# capDisChg_v1.net
KiCad netlist of a schematic drawn in EasyEDA Pro
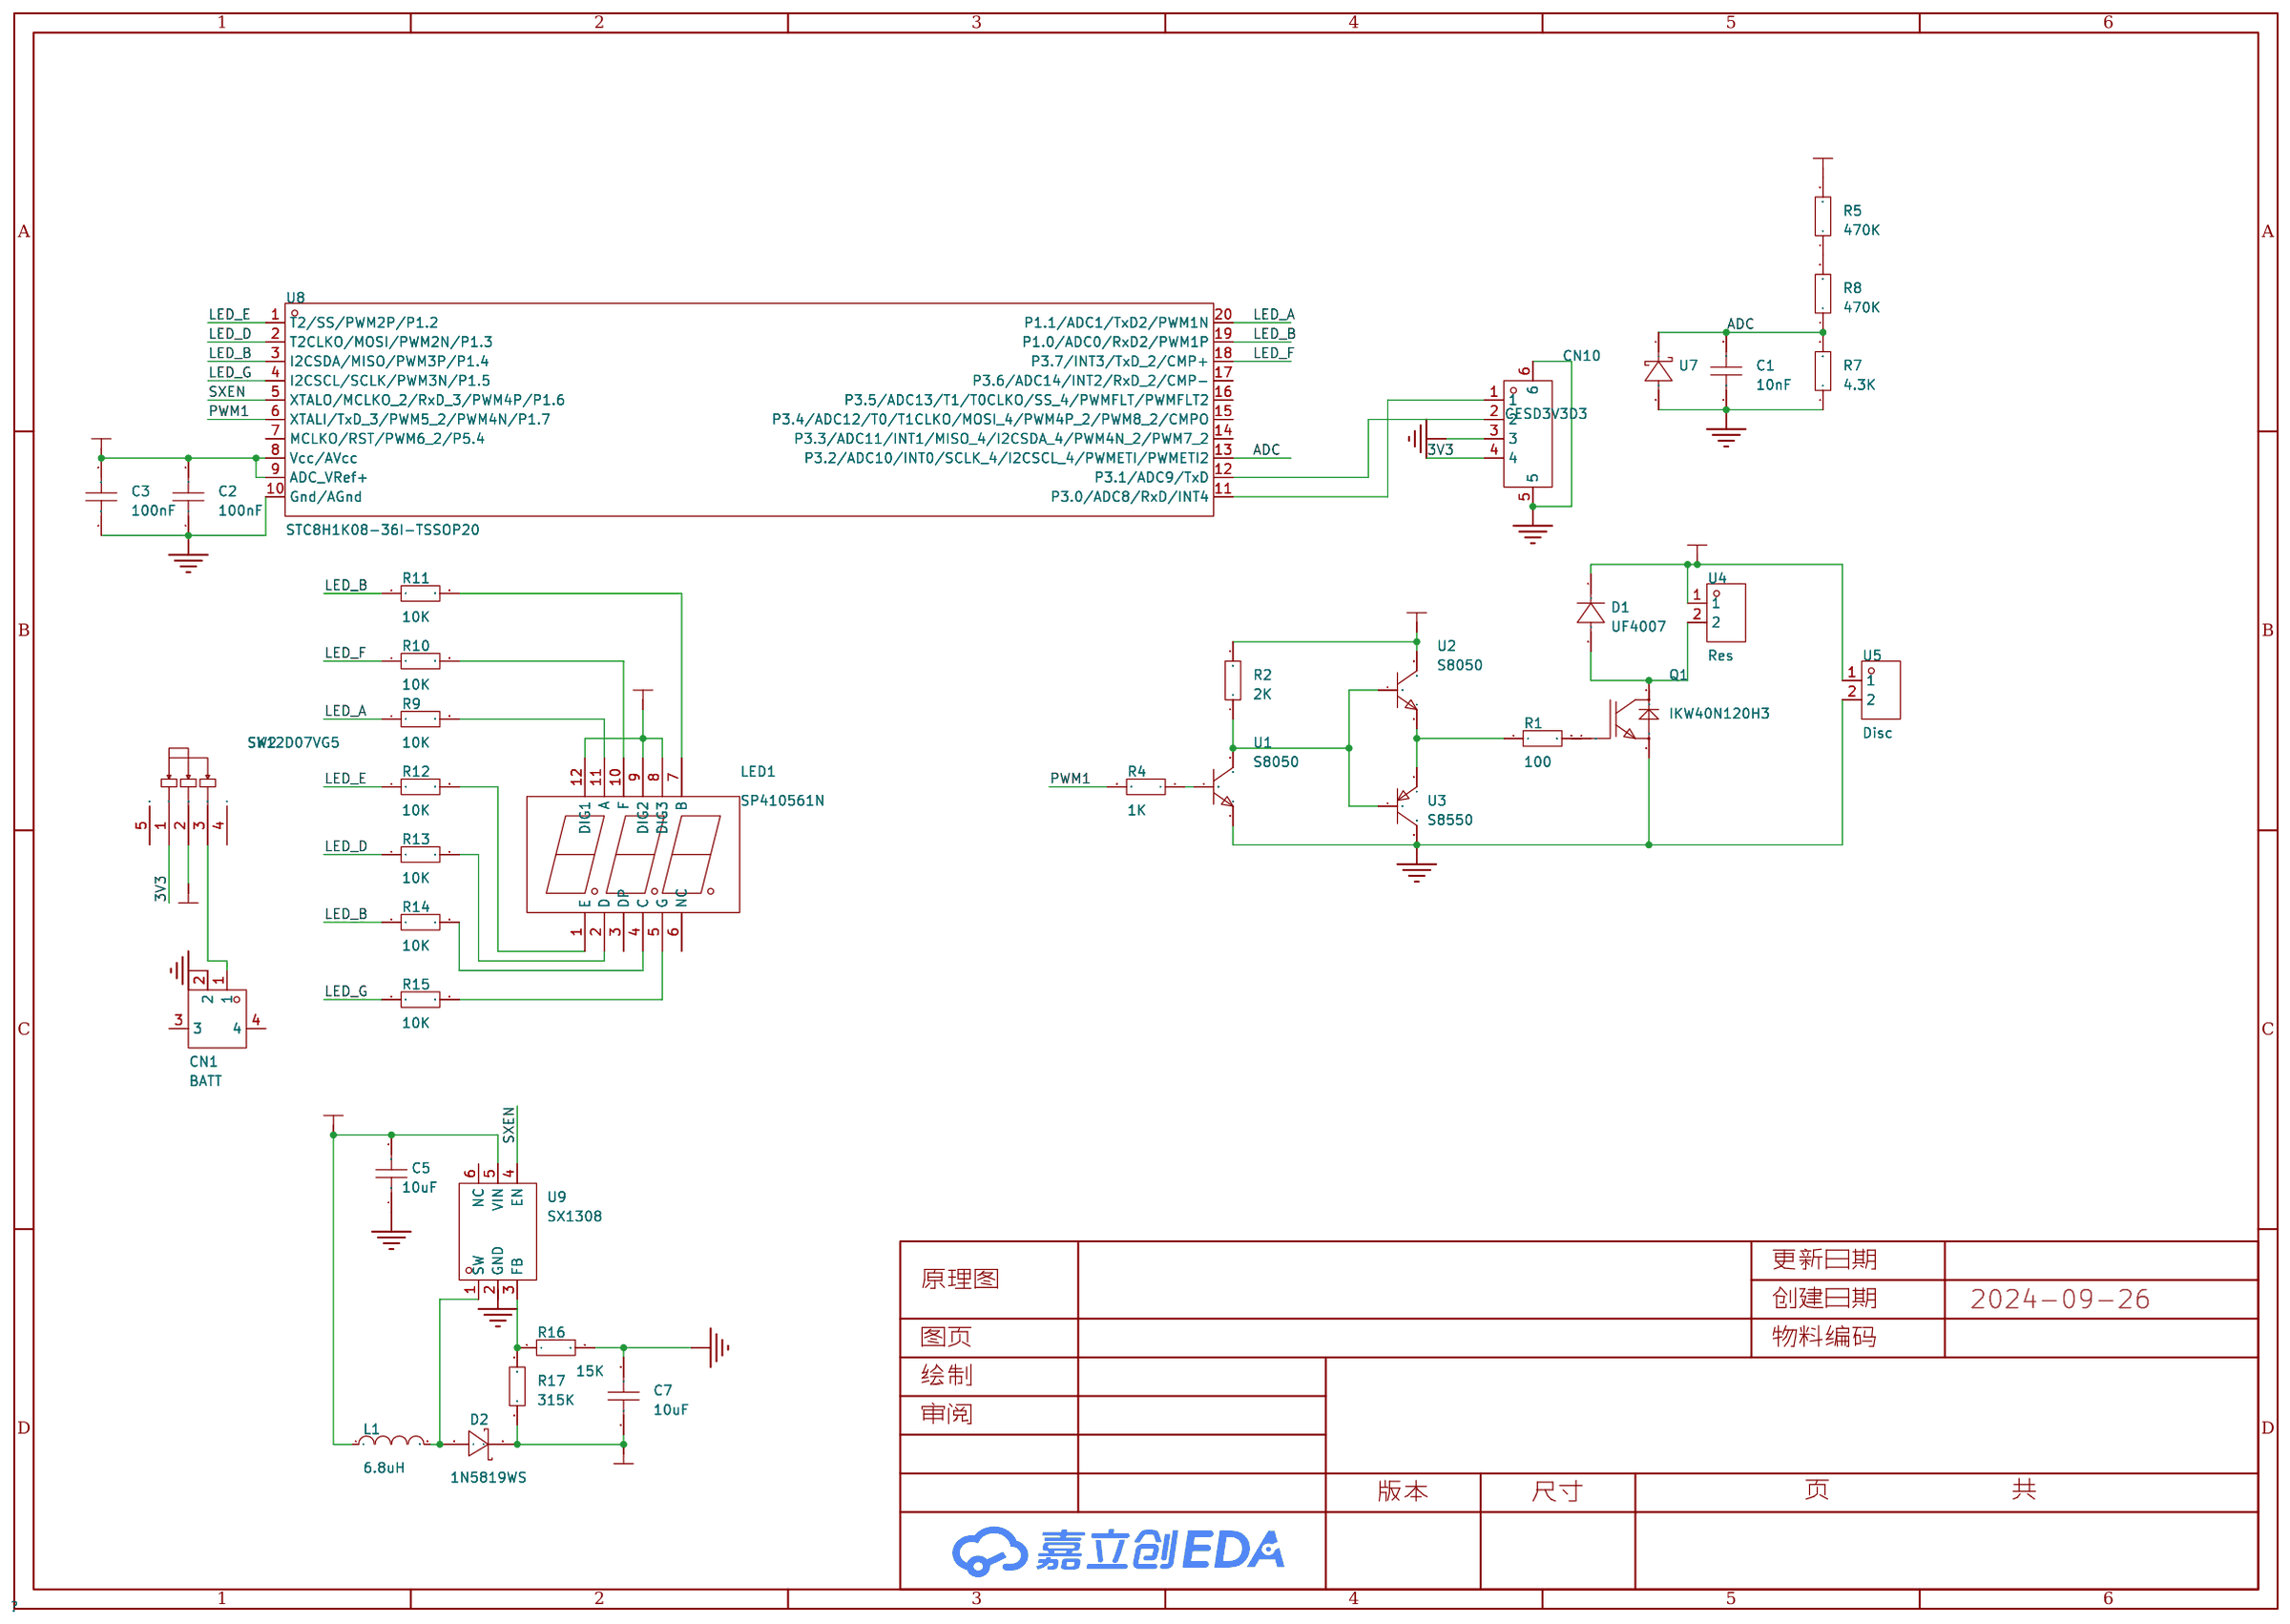
[diagram p0: schematic sheet]

(export (version "E")
  (design (tool "Eeschema 10.0.6"))
  (components
    (comp (ref "C1")
      (value "10nF")
      (footprint "easyedapro:C0805")
      (libsource (lib "easyedapro") (part "CapAcitance"))
    )
    (comp (ref "C2")
      (value "100nF")
      (footprint "easyedapro:C0805")
      (libsource (lib "easyedapro") (part "CapAcitance"))
    )
    (comp (ref "C3")
      (value "100nF")
      (footprint "easyedapro:C0805")
      (libsource (lib "easyedapro") (part "CapAcitance"))
    )
    (comp (ref "C5")
      (value "10uF")
      (footprint "easyedapro:C0805")
      (libsource (lib "easyedapro") (part "CapAcitance"))
    )
    (comp (ref "C7")
      (value "10uF")
      (footprint "easyedapro:C0805")
      (libsource (lib "easyedapro") (part "CapAcitance"))
    )
    (comp (ref "CN1")
      (value "BATT")
      (footprint "easyedapro:CONN-TH_2P-P1.25_XUNPU_WAFER-GH1.25-2PWB")
      (description "插针结构:1x2P;间距:1.25mm;安装方式:卧贴;参考系列:GH;总PIN数:2P;排数:1;每排PIN数:2;额定电流:1A;工作温度范围:-25°C~+85°C;")
      (fields (field (name "Manufacturer") "XUNPU(讯普)"))
      (libsource (lib "easyedapro") (part "WAFER-GH1.25-2PWB"))
    )
    (comp (ref "CN10")
      (value "WAFER-GH1.25-4PLB")
      (footprint "easyedapro:CONN-SMD_4P-P1.25_XUNPU_WAFER-GH1.25-4PLB")
      (description "插针结构:1x4P;间距:1.25mm;安装方式:立贴;参考系列:GH;总PIN数:4P;排数:1;每排PIN数:4;额定电流:1A;工作温度范围:-25°C~+85°C;")
      (fields (field (name "Manufacturer") "XUNPU(讯普)"))
      (libsource (lib "easyedapro") (part "WAFER-GH1.25-4PLB"))
    )
    (comp (ref "D1")
      (value "UF4007")
      (footprint "easyedapro:DO-41_BD2.4-L4.7-P8.70-D0.9-RD")
      (description "二极管配置:-;正向压降(Vf):1.7V@1A;直流反向耐压(Vr):1kV;整流电流:1A;反向恢复时间(trr):75ns;")
      (fields (field (name "Manufacturer") "MDD(辰达半导体)"))
      (libsource (lib "easyedapro") (part "UF4007_C960666"))
    )
    (comp (ref "D2")
      (value "1N5819WS")
      (footprint "easyedapro:SOD-323_L1.8-W1.3-LS2.5-RD")
      (description "正向压降(Vf):600mV@1A;直流反向耐压(Vr):40V;平均整流电流(Io):1A;")
      (fields (field (name "Manufacturer") "Hottech(合科泰)"))
      (libsource (lib "easyedapro") (part "1N5819WS"))
    )
    (comp (ref "L1")
      (value "6.8uH")
      (footprint "easyedapro:L1206")
      (libsource (lib "easyedapro") (part "CMI321609VR27KT"))
    )
    (comp (ref "LED1")
      (value "SP410561N")
      (footprint "easyedapro:LED-SEG-TH_12P-L37.6-W19.0-P2.54-S15.24-BL")
      (description "数码管位数:3位;发光颜色:红色;LED极性:共阳极;数字/字母大小(英寸):0.56;")
      (fields (field (name "Manufacturer") "ARKLED(方舟)"))
      (libsource (lib "easyedapro") (part "SP410561N"))
    )
    (comp (ref "Q1")
      (value "IKW40N120H3")
      (footprint "easyedapro:TO-247AC-3_L15.8-W5.0-P5.46-L")
      (description "40A1200V 英飞凌IGBT，广泛应用于电磁炉，电机，电焊机行业。")
      (fields (field (name "Manufacturer") "Infineon(英飞凌)"))
      (libsource (lib "easyedapro") (part "IKW40N120H3"))
    )
    (comp (ref "R1") (value "100") (footprint "easyedapro:R0603") (libsource (lib "easyedapro") (part "电阻")))
    (comp (ref "R2") (value "2K") (footprint "easyedapro:R0603") (libsource (lib "easyedapro") (part "电阻")))
    (comp (ref "R4") (value "1K") (footprint "easyedapro:R0603") (libsource (lib "easyedapro") (part "电阻")))
    (comp (ref "R5") (value "470K") (footprint "easyedapro:R0603") (libsource (lib "easyedapro") (part "电阻")))
    (comp (ref "R7") (value "4.3K") (footprint "easyedapro:R0603") (libsource (lib "easyedapro") (part "电阻")))
    (comp (ref "R8") (value "470K") (footprint "easyedapro:R0603") (libsource (lib "easyedapro") (part "电阻")))
    (comp (ref "R9") (value "10K") (footprint "easyedapro:R0603") (libsource (lib "easyedapro") (part "电阻")))
    (comp (ref "R10") (value "10K") (footprint "easyedapro:R0603") (libsource (lib "easyedapro") (part "电阻")))
    (comp (ref "R11") (value "10K") (footprint "easyedapro:R0603") (libsource (lib "easyedapro") (part "电阻")))
    (comp (ref "R12") (value "10K") (footprint "easyedapro:R0603") (libsource (lib "easyedapro") (part "电阻")))
    (comp (ref "R13") (value "10K") (footprint "easyedapro:R0603") (libsource (lib "easyedapro") (part "电阻")))
    (comp (ref "R14") (value "10K") (footprint "easyedapro:R0603") (libsource (lib "easyedapro") (part "电阻")))
    (comp (ref "R15") (value "10K") (footprint "easyedapro:R0603") (libsource (lib "easyedapro") (part "电阻")))
    (comp (ref "R16") (value "15K") (footprint "easyedapro:R0603") (libsource (lib "easyedapro") (part "电阻")))
    (comp (ref "R17")
      (value "315K")
      (footprint "easyedapro:R0603")
      (libsource (lib "easyedapro") (part "电阻"))
    )
    (comp (ref "SW2")
      (value "SK12D07VG5")
      (footprint "easyedapro:SW-TH_SK12D07VG5")
      (description "电路结构:单刀双掷;安装方式:侧插;开关颜色:-;额定电流(DC):500mA;额定电压(DC):50V;额定电流(AC):-;额定电压(AC):-;机械寿命:5千次;")
      (fields (field (name "Manufacturer") "SHOU HAN(首韩)"))
      (libsource (lib "easyedapro") (part "SK12D07VG5"))
    )
    (comp (ref "U1")
      (value "S8050")
      (footprint "easyedapro:SOT-23-3_L2.9-W1.3-P1.90-LS2.3-BR")
      (description "晶体管类型:NPN;集电极电流(Ic):500mA;集射极击穿电压(Vceo):25V;功率(Pd):300mW;直流电流增益(hFE@Ic,Vce):120@50mA,1.0V;")
      (fields (field (name "Manufacturer") "宏迦橙"))
      (libsource (lib "easyedapro") (part "S8050_C20069125"))
    )
    (comp (ref "U2")
      (value "S8050")
      (footprint "easyedapro:SOT-23-3_L2.9-W1.3-P1.90-LS2.3-BR")
      (description "晶体管类型:NPN;集电极电流(Ic):500mA;集射极击穿电压(Vceo):25V;功率(Pd):300mW;直流电流增益(hFE@Ic,Vce):120@50mA,1.0V;")
      (fields (field (name "Manufacturer") "宏迦橙"))
      (libsource (lib "easyedapro") (part "S8050_C20069125"))
    )
    (comp (ref "U3")
      (value "S8550")
      (footprint "easyedapro:SOT-23-3_L2.9-W1.3-P1.90-LS2.4-BR")
      (description "晶体管类型:PNP;集电极电流(Ic):500mA;集射极击穿电压(Vceo):25V;功率(Pd):300mW;直流电流增益(hFE@Ic,Vce):120@500mA,1.0V;")
      (fields (field (name "Manufacturer") "宏迦橙"))
      (libsource (lib "easyedapro") (part "S8550_C20069126"))
    )
    (comp (ref "U4")
      (value "Res")
      (footprint "easyedapro:CONN-TH_VH3.96-3A2")
      (fields (field (name "Manufacturer") "SHOU HAN(首韩)"))
      (libsource (lib "easyedapro") (part "VH3.96-3P(2P) ZZ"))
    )
    (comp (ref "U5")
      (value "Disc")
      (footprint "easyedapro:CONN-TH_VH3.96-3A2")
      (fields (field (name "Manufacturer") "SHOU HAN(首韩)"))
      (libsource (lib "easyedapro") (part "VH3.96-3P(2P) ZZ"))
    )
    (comp (ref "U7")
      (value "CESD3V3D3")
      (footprint "easyedapro:SOD-523_L1.2-W0.8-LS1.6-RD")
      (fields (field (name "Manufacturer") "TECH PUBLIC(台舟)"))
      (libsource (lib "easyedapro") (part "CESD3V3D3_C20611855"))
    )
    (comp (ref "U8")
      (value "STC8H1K08-36I-TSSOP20")
      (footprint "easyedapro:TSSOP-20_L6.5-W4.4-P0.65-LS6.4-BL")
      (description "CPU内核:51系列;程序存储容量:8KB;RAM总容量:1.25KB;GPIO端口数量:17;工作电压范围:1.9V~5.5V;CPU最大主频:-;程序存储器类型:FLASH;")
      (fields (field (name "Manufacturer") "STC(宏晶)"))
      (libsource (lib "easyedapro") (part "STC8H1K08-36I-TSSOP20"))
    )
    (comp (ref "U9")
      (value "SX1308")
      (footprint "easyedapro:SOT-23-6_L2.9-W1.6-P0.95-LS2.8-BL")
      (description "功能类型:升压型;输入电压:2V~24V;输出电压:28V;输出电流(最大值):-;")
      (fields (field (name "Manufacturer") "SX(硕芯科技)"))
      (libsource (lib "easyedapro") (part "SX1308"))
    )
  )
  (nets
    (net (code "1") (name "+12V") (class "Default")
      (node (ref "C7") (pin "1") (pinfunction "1_1") (pintype "input"))
      (node (ref "D2") (pin "1") (pinfunction "K_1") (pintype "unspecified"))
      (node (ref "R17") (pin "1") (pinfunction "1_1") (pintype "input"))
      (node (ref "R2") (pin "2") (pinfunction "2_2") (pintype "input"))
      (node (ref "U2") (pin "3") (pinfunction "C_3") (pintype "input"))
    )
    (net (code "2") (name "/3V3") (class "Default")
      (node (ref "CN10") (pin "4") (pinfunction "4_4") (pintype "unspecified"))
      (node (ref "SW2") (pin "1") (pinfunction "1_1") (pintype "unspecified"))
    )
    (net (code "3") (name "/ADC") (class "Default")
      (node (ref "C1") (pin "2") (pinfunction "2_2") (pintype "input"))
      (node (ref "R7") (pin "2") (pinfunction "2_2") (pintype "input"))
      (node (ref "R8") (pin "1") (pinfunction "1_1") (pintype "input"))
      (node (ref "U7") (pin "1") (pinfunction "1_1") (pintype "unspecified"))
      (node (ref "U8") (pin "13") (pinfunction "P3.2/ADC10/INT0/SCLK_4/I2CSCL_4/PWMETI/PWMETI2_13") (pintype "unspecified"))
    )
    (net (code "4") (name "/LED_A") (class "Default")
      (node (ref "R9") (pin "1") (pinfunction "1_1") (pintype "input"))
      (node (ref "U8") (pin "20") (pinfunction "P1.1/ADC1/TxD2/PWM1N_20") (pintype "unspecified"))
    )
    (net (code "5") (name "/LED_B") (class "Default")
      (node (ref "R11") (pin "1") (pinfunction "1_1") (pintype "input"))
      (node (ref "R14") (pin "1") (pinfunction "1_1") (pintype "input"))
      (node (ref "U8") (pin "19") (pinfunction "P1.0/ADC0/RxD2/PWM1P_19") (pintype "unspecified"))
      (node (ref "U8") (pin "3") (pinfunction "I2CSDA/MISO/PWM3P/P1.4_3") (pintype "unspecified"))
    )
    (net (code "6") (name "/LED_D") (class "Default")
      (node (ref "R13") (pin "1") (pinfunction "1_1") (pintype "input"))
      (node (ref "U8") (pin "2") (pinfunction "T2CLKO/MOSI/PWM2N/P1.3_2") (pintype "unspecified"))
    )
    (net (code "7") (name "/LED_E") (class "Default")
      (node (ref "R12") (pin "1") (pinfunction "1_1") (pintype "input"))
      (node (ref "U8") (pin "1") (pinfunction "T2/SS/PWM2P/P1.2_1") (pintype "unspecified"))
    )
    (net (code "8") (name "/LED_F") (class "Default")
      (node (ref "R10") (pin "1") (pinfunction "1_1") (pintype "input"))
      (node (ref "U8") (pin "18") (pinfunction "P3.7/INT3/TxD_2/CMP+_18") (pintype "unspecified"))
    )
    (net (code "9") (name "/LED_G") (class "Default")
      (node (ref "R15") (pin "1") (pinfunction "1_1") (pintype "input"))
      (node (ref "U8") (pin "4") (pinfunction "I2CSCL/SCLK/PWM3N/P1.5_4") (pintype "unspecified"))
    )
    (net (code "10") (name "/PWM1") (class "Default")
      (node (ref "R4") (pin "2") (pinfunction "2_2") (pintype "input"))
      (node (ref "U8") (pin "6") (pinfunction "XTALI/TxD_3/PWM5_2/PWM4N/P1.7_6") (pintype "unspecified"))
    )
    (net (code "11") (name "/SXEN") (class "Default")
      (node (ref "U8") (pin "5") (pinfunction "XTALO/MCLKO_2/RxD_3/PWM4P/P1.6_5") (pintype "unspecified"))
      (node (ref "U9") (pin "4") (pinfunction "EN_4") (pintype "input"))
    )
    (net (code "12") (name "GND") (class "Default")
      (node (ref "C1") (pin "1") (pinfunction "1_1") (pintype "input"))
      (node (ref "C2") (pin "1") (pinfunction "1_1") (pintype "input"))
      (node (ref "C3") (pin "1") (pinfunction "1_1") (pintype "input"))
      (node (ref "C5") (pin "1") (pinfunction "1_1") (pintype "input"))
      (node (ref "C7") (pin "2") (pinfunction "2_2") (pintype "input"))
      (node (ref "CN1") (pin "2") (pinfunction "2_2") (pintype "unspecified"))
      (node (ref "CN10") (pin "3") (pinfunction "3_3") (pintype "unspecified"))
      (node (ref "CN10") (pin "5") (pinfunction "5_5") (pintype "unspecified"))
      (node (ref "CN10") (pin "6") (pinfunction "6_6") (pintype "unspecified"))
      (node (ref "Q1") (pin "3") (pinfunction "E_3") (pintype "input"))
      (node (ref "R16") (pin "2") (pinfunction "2_2") (pintype "input"))
      (node (ref "R7") (pin "1") (pinfunction "1_1") (pintype "input"))
      (node (ref "U1") (pin "2") (pinfunction "E_2") (pintype "input"))
      (node (ref "U3") (pin "3") (pinfunction "C_3") (pintype "input"))
      (node (ref "U5") (pin "2") (pinfunction "2_2") (pintype "unspecified"))
      (node (ref "U7") (pin "2") (pinfunction "2_2") (pintype "unspecified"))
      (node (ref "U8") (pin "10") (pinfunction "Gnd/AGnd_10") (pintype "unspecified"))
      (node (ref "U9") (pin "2") (pinfunction "GND_2") (pintype "input"))
    )
    (net (code "13") (name "MCU_VCC") (class "Default")
      (node (ref "C2") (pin "2") (pinfunction "2_2") (pintype "input"))
      (node (ref "C3") (pin "2") (pinfunction "2_2") (pintype "input"))
      (node (ref "C5") (pin "2") (pinfunction "2_2") (pintype "input"))
      (node (ref "L1") (pin "1") (pinfunction "1_1") (pintype "unspecified"))
      (node (ref "LED1") (pin "12") (pinfunction "DIG1_12") (pintype "input"))
      (node (ref "LED1") (pin "8") (pinfunction "DIG3_8") (pintype "input"))
      (node (ref "LED1") (pin "9") (pinfunction "DIG2_9") (pintype "input"))
      (node (ref "SW2") (pin "2") (pinfunction "2_2") (pintype "unspecified"))
      (node (ref "U8") (pin "8") (pinfunction "Vcc/AVcc_8") (pintype "unspecified"))
      (node (ref "U8") (pin "9") (pinfunction "ADC_VRef+_9") (pintype "unspecified"))
      (node (ref "U9") (pin "5") (pinfunction "VIN_5") (pintype "input"))
    )
    (net (code "14") (name "Net-(CN1-Pad1)") (class "Default")
      (node (ref "CN1") (pin "1") (pinfunction "1_1") (pintype "unspecified"))
      (node (ref "SW2") (pin "3") (pinfunction "3_3") (pintype "unspecified"))
    )
    (net (code "15") (name "Net-(D1-A)") (class "Default")
      (node (ref "D1") (pin "2") (pinfunction "A_2") (pintype "unspecified"))
      (node (ref "Q1") (pin "2") (pinfunction "C_2") (pintype "input"))
      (node (ref "U4") (pin "2") (pinfunction "2_2") (pintype "unspecified"))
    )
    (net (code "16") (name "Net-(D2-A)") (class "Default")
      (node (ref "D2") (pin "2") (pinfunction "A_2") (pintype "unspecified"))
      (node (ref "L1") (pin "2") (pinfunction "2_2") (pintype "unspecified"))
      (node (ref "U9") (pin "1") (pinfunction "SW_1") (pintype "input"))
    )
    (net (code "17") (name "Net-(LED1-A)") (class "Default")
      (node (ref "LED1") (pin "11") (pinfunction "A_11") (pintype "input"))
      (node (ref "R9") (pin "2") (pinfunction "2_2") (pintype "input"))
    )
    (net (code "18") (name "Net-(LED1-B)") (class "Default")
      (node (ref "LED1") (pin "7") (pinfunction "B_7") (pintype "input"))
      (node (ref "R11") (pin "2") (pinfunction "2_2") (pintype "input"))
    )
    (net (code "19") (name "Net-(LED1-C)") (class "Default")
      (node (ref "LED1") (pin "4") (pinfunction "C_4") (pintype "input"))
      (node (ref "R14") (pin "2") (pinfunction "2_2") (pintype "input"))
    )
    (net (code "20") (name "Net-(LED1-D)") (class "Default")
      (node (ref "LED1") (pin "2") (pinfunction "D_2") (pintype "input"))
      (node (ref "R13") (pin "2") (pinfunction "2_2") (pintype "input"))
    )
    (net (code "21") (name "Net-(LED1-E)") (class "Default")
      (node (ref "LED1") (pin "1") (pinfunction "E_1") (pintype "input"))
      (node (ref "R12") (pin "2") (pinfunction "2_2") (pintype "input"))
    )
    (net (code "22") (name "Net-(LED1-F)") (class "Default")
      (node (ref "LED1") (pin "10") (pinfunction "F_10") (pintype "input"))
      (node (ref "R10") (pin "2") (pinfunction "2_2") (pintype "input"))
    )
    (net (code "23") (name "Net-(LED1-G)") (class "Default")
      (node (ref "LED1") (pin "5") (pinfunction "G_5") (pintype "input"))
      (node (ref "R15") (pin "2") (pinfunction "2_2") (pintype "input"))
    )
    (net (code "24") (name "Net-(Q1-G)") (class "Default")
      (node (ref "Q1") (pin "1") (pinfunction "G_1") (pintype "input"))
      (node (ref "R1") (pin "2") (pinfunction "2_2") (pintype "input"))
    )
    (net (code "25") (name "Net-(R5-Pad1)") (class "Default")
      (node (ref "R5") (pin "1") (pinfunction "1_1") (pintype "input"))
      (node (ref "R8") (pin "2") (pinfunction "2_2") (pintype "input"))
    )
    (net (code "26") (name "Net-(U1-B)") (class "Default")
      (node (ref "R4") (pin "1") (pinfunction "1_1") (pintype "input"))
      (node (ref "U1") (pin "1") (pinfunction "B_1") (pintype "input"))
    )
    (net (code "27") (name "Net-(U1-C)") (class "Default")
      (node (ref "R2") (pin "1") (pinfunction "1_1") (pintype "input"))
      (node (ref "U1") (pin "3") (pinfunction "C_3") (pintype "input"))
      (node (ref "U2") (pin "1") (pinfunction "B_1") (pintype "input"))
      (node (ref "U3") (pin "1") (pinfunction "B_1") (pintype "input"))
    )
    (net (code "28") (name "Net-(U2-E)") (class "Default")
      (node (ref "R1") (pin "1") (pinfunction "1_1") (pintype "input"))
      (node (ref "U2") (pin "2") (pinfunction "E_2") (pintype "input"))
      (node (ref "U3") (pin "2") (pinfunction "E_2") (pintype "input"))
    )
    (net (code "29") (name "Net-(U8-P3.0{slash}ADC8{slash}RxD{slash}INT4)") (class "Default")
      (node (ref "CN10") (pin "1") (pinfunction "1_1") (pintype "unspecified"))
      (node (ref "U8") (pin "11") (pinfunction "P3.0/ADC8/RxD/INT4_11") (pintype "unspecified"))
    )
    (net (code "30") (name "Net-(U8-P3.1{slash}ADC9{slash}TxD)") (class "Default")
      (node (ref "CN10") (pin "2") (pinfunction "2_2") (pintype "unspecified"))
      (node (ref "U8") (pin "12") (pinfunction "P3.1/ADC9/TxD_12") (pintype "unspecified"))
    )
    (net (code "31") (name "Net-(U9-FB)") (class "Default")
      (node (ref "R16") (pin "1") (pinfunction "1_1") (pintype "input"))
      (node (ref "R17") (pin "2") (pinfunction "2_2") (pintype "input"))
      (node (ref "U9") (pin "3") (pinfunction "FB_3") (pintype "input"))
    )
    (net (code "32") (name "VBUS+") (class "Default")
      (node (ref "D1") (pin "1") (pinfunction "K_1") (pintype "unspecified"))
      (node (ref "R5") (pin "2") (pinfunction "2_2") (pintype "input"))
      (node (ref "U4") (pin "1") (pinfunction "1_1") (pintype "unspecified"))
      (node (ref "U5") (pin "1") (pinfunction "1_1") (pintype "unspecified"))
    )
    (net (code "33") (name "unconnected-(CN1-Pad3)") (class "Default")
      (node (ref "CN1") (pin "3") (pinfunction "3_3") (pintype "unspecified"))
    )
    (net (code "34") (name "unconnected-(CN1-Pad4)") (class "Default")
      (node (ref "CN1") (pin "4") (pinfunction "4_4") (pintype "unspecified"))
    )
    (net (code "35") (name "unconnected-(LED1-DP-Pad3)") (class "Default")
      (node (ref "LED1") (pin "3") (pinfunction "DP_3") (pintype "input"))
    )
    (net (code "36") (name "unconnected-(LED1-NC-Pad6)") (class "Default")
      (node (ref "LED1") (pin "6") (pinfunction "NC_6") (pintype "input"))
    )
    (net (code "37") (name "unconnected-(SW2-Pad4)") (class "Default")
      (node (ref "SW2") (pin "4") (pinfunction "4_4") (pintype "unspecified"))
    )
    (net (code "38") (name "unconnected-(SW2-Pad5)") (class "Default")
      (node (ref "SW2") (pin "5") (pinfunction "5_5") (pintype "unspecified"))
    )
    (net (code "39") (name "unconnected-(U8-MCLKO{slash}RST{slash}PWM6_2{slash}P5.4-Pad7)") (class "Default")
      (node (ref "U8") (pin "7") (pinfunction "MCLKO/RST/PWM6_2/P5.4_7") (pintype "unspecified"))
    )
    (net (code "40") (name "unconnected-(U8-P3.3{slash}ADC11{slash}INT1{slash}MISO_4{slash}I2CSDA_4{slash}PWM4N_2{slash}PWM7_2-Pad14)") (class "Default")
      (node (ref "U8") (pin "14") (pinfunction "P3.3/ADC11/INT1/MISO_4/I2CSDA_4/PWM4N_2/PWM7_2_14") (pintype "unspecified"))
    )
    (net (code "41") (name "unconnected-(U8-P3.4{slash}ADC12{slash}T0{slash}T1CLKO{slash}MOSI_4{slash}PWM4P_2{slash}PWM8_2{slash}CMPO-Pad15)") (class "Default")
      (node (ref "U8") (pin "15") (pinfunction "P3.4/ADC12/T0/T1CLKO/MOSI_4/PWM4P_2/PWM8_2/CMPO_15") (pintype "unspecified"))
    )
    (net (code "42") (name "unconnected-(U8-P3.5{slash}ADC13{slash}T1{slash}T0CLKO{slash}SS_4{slash}PWMFLT{slash}PWMFLT2-Pad16)") (class "Default")
      (node (ref "U8") (pin "16") (pinfunction "P3.5/ADC13/T1/T0CLKO/SS_4/PWMFLT/PWMFLT2_16") (pintype "unspecified"))
    )
    (net (code "43") (name "unconnected-(U8-P3.6{slash}ADC14{slash}INT2{slash}RxD_2{slash}CMP--Pad17)") (class "Default")
      (node (ref "U8") (pin "17") (pinfunction "P3.6/ADC14/INT2/RxD_2/CMP-_17") (pintype "unspecified"))
    )
    (net (code "44") (name "unconnected-(U9-NC-Pad6)") (class "Default")
      (node (ref "U9") (pin "6") (pinfunction "NC_6") (pintype "input"))
    )
  )
)
